# GS2011M.net
KiCad netlist of a schematic drawn in EAGLE
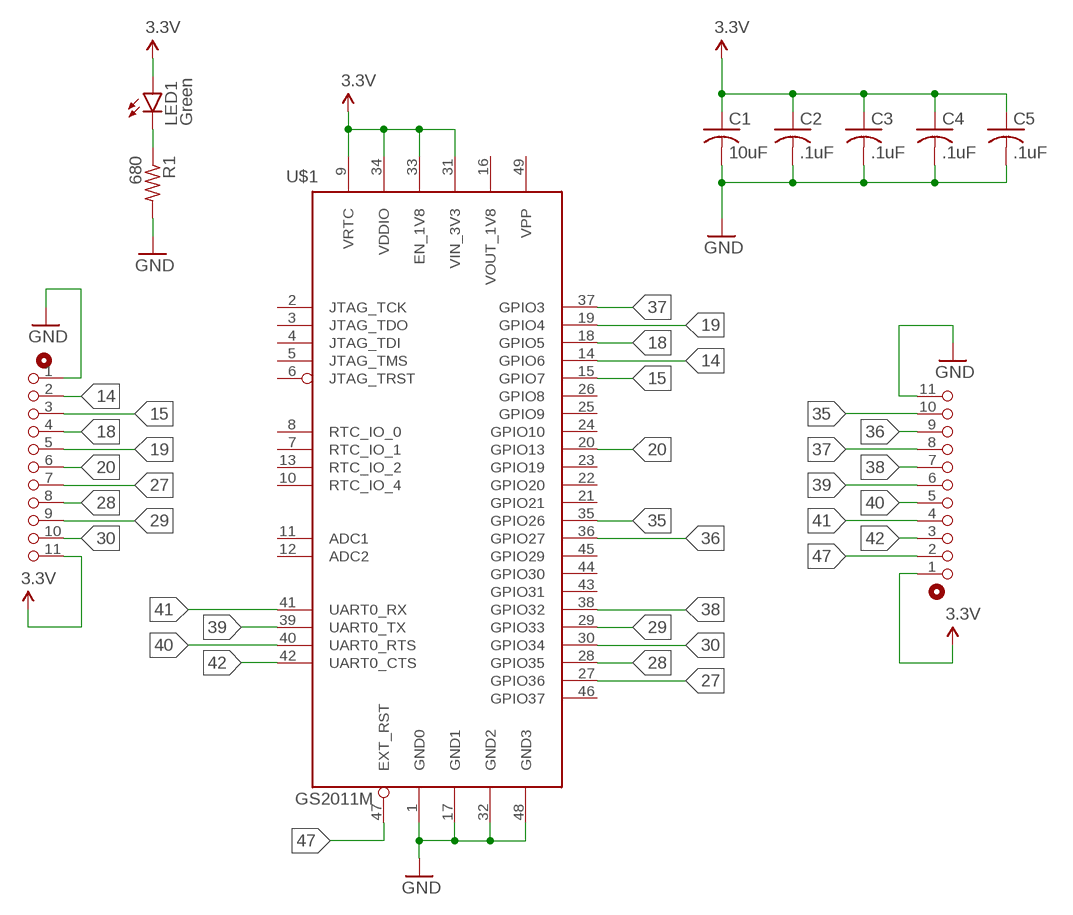
[diagram p0: schematic, sheet 1]

(export (version "E")
  (design (tool "Eeschema 10.0.6"))
  (components
    (comp (ref "C1")
      (value "10uF")
      (footprint "eagle-import:0603_CAP")
      (libsource (lib "eagle-import") (part "CAP0603"))
    )
    (comp (ref "C2")
      (value ".1uF")
      (footprint "eagle-import:0603_CAP")
      (libsource (lib "eagle-import") (part "CAP0603"))
    )
    (comp (ref "C3")
      (value ".1uF")
      (footprint "eagle-import:0603_CAP")
      (libsource (lib "eagle-import") (part "CAP0603"))
    )
    (comp (ref "C4")
      (value ".1uF")
      (footprint "eagle-import:0603_CAP")
      (libsource (lib "eagle-import") (part "CAP0603"))
    )
    (comp (ref "C5")
      (value ".1uF")
      (footprint "eagle-import:0603_CAP")
      (libsource (lib "eagle-import") (part "CAP0603"))
    )
    (comp (ref "LED1")
      (value "Green")
      (footprint "eagle-import:0603_LED")
      (fields (field (name "MANF") "Avago Technologies"))
      (libsource (lib "eagle-import") (part "LED0603"))
    )
    (comp (ref "P1")
      (value "PIN-11X1")
      (footprint "eagle-import:PIN-11X1")
      (libsource (lib "eagle-import") (part "PIN-11X1"))
    )
    (comp (ref "P2")
      (value "PIN-11X1")
      (footprint "eagle-import:PIN-11X1")
      (libsource (lib "eagle-import") (part "PIN-11X1"))
    )
    (comp (ref "R1")
      (value "680")
      (footprint "eagle-import:0603_RESISTOR")
      (libsource (lib "eagle-import") (part "RESISTOR0603"))
    )
    (comp (ref "U$1")
      (value "GS2011M")
      (footprint "eagle-import:GS2011M")
      (libsource (lib "eagle-import") (part "GS2011M"))
    )
  )
  (nets
    (net (code "1") (name "/VOUT_1V8") (class "Default")
      (node (ref "U$1") (pin "16") (pinfunction "VOUT_1V8_16") (pintype "power_in"))
    )
    (net (code "2") (name "3.3V") (class "Default")
      (node (ref "C1") (pin "1") (pinfunction "1_1") (pintype "passive"))
      (node (ref "C2") (pin "1") (pinfunction "1_1") (pintype "passive"))
      (node (ref "C3") (pin "1") (pinfunction "1_1") (pintype "passive"))
      (node (ref "C4") (pin "1") (pinfunction "1_1") (pintype "passive"))
      (node (ref "C5") (pin "1") (pinfunction "1_1") (pintype "passive"))
      (node (ref "LED1") (pin "A") (pinfunction "A_A") (pintype "passive"))
      (node (ref "P1") (pin "11") (pinfunction "11_11") (pintype "passive"))
      (node (ref "P2") (pin "1") (pinfunction "1_1") (pintype "passive"))
      (node (ref "U$1") (pin "31") (pinfunction "VIN_3V3_31") (pintype "power_in"))
      (node (ref "U$1") (pin "33") (pinfunction "EN_1V8_33") (pintype "power_in"))
      (node (ref "U$1") (pin "34") (pinfunction "VDDIO_34") (pintype "power_in"))
      (node (ref "U$1") (pin "9") (pinfunction "VRTC_9") (pintype "power_in"))
    )
    (net (code "3") (name "14") (class "Default")
      (node (ref "P1") (pin "2") (pinfunction "2_2") (pintype "passive"))
      (node (ref "U$1") (pin "14") (pinfunction "GPIO6_14") (pintype "bidirectional"))
    )
    (net (code "4") (name "15") (class "Default")
      (node (ref "P1") (pin "3") (pinfunction "3_3") (pintype "passive"))
      (node (ref "U$1") (pin "15") (pinfunction "GPIO7_15") (pintype "bidirectional"))
    )
    (net (code "5") (name "18") (class "Default")
      (node (ref "P1") (pin "4") (pinfunction "4_4") (pintype "passive"))
      (node (ref "U$1") (pin "18") (pinfunction "GPIO5_18") (pintype "bidirectional"))
    )
    (net (code "6") (name "19") (class "Default")
      (node (ref "P1") (pin "5") (pinfunction "5_5") (pintype "passive"))
      (node (ref "U$1") (pin "19") (pinfunction "GPIO4_19") (pintype "bidirectional"))
    )
    (net (code "7") (name "20") (class "Default")
      (node (ref "P1") (pin "6") (pinfunction "6_6") (pintype "passive"))
      (node (ref "U$1") (pin "20") (pinfunction "GPIO13_20") (pintype "bidirectional"))
    )
    (net (code "8") (name "27") (class "Default")
      (node (ref "P1") (pin "7") (pinfunction "7_7") (pintype "passive"))
      (node (ref "U$1") (pin "27") (pinfunction "GPIO36_27") (pintype "bidirectional"))
    )
    (net (code "9") (name "28") (class "Default")
      (node (ref "P1") (pin "8") (pinfunction "8_8") (pintype "passive"))
      (node (ref "U$1") (pin "28") (pinfunction "GPIO35_28") (pintype "bidirectional"))
    )
    (net (code "10") (name "29") (class "Default")
      (node (ref "P1") (pin "9") (pinfunction "9_9") (pintype "passive"))
      (node (ref "U$1") (pin "29") (pinfunction "GPIO33_29") (pintype "bidirectional"))
    )
    (net (code "11") (name "30") (class "Default")
      (node (ref "P1") (pin "10") (pinfunction "10_10") (pintype "passive"))
      (node (ref "U$1") (pin "30") (pinfunction "GPIO34_30") (pintype "bidirectional"))
    )
    (net (code "12") (name "35") (class "Default")
      (node (ref "P2") (pin "10") (pinfunction "10_10") (pintype "passive"))
      (node (ref "U$1") (pin "35") (pinfunction "GPIO26_35") (pintype "bidirectional"))
    )
    (net (code "13") (name "36") (class "Default")
      (node (ref "P2") (pin "9") (pinfunction "9_9") (pintype "passive"))
      (node (ref "U$1") (pin "36") (pinfunction "GPIO27_36") (pintype "bidirectional"))
    )
    (net (code "14") (name "37") (class "Default")
      (node (ref "P2") (pin "8") (pinfunction "8_8") (pintype "passive"))
      (node (ref "U$1") (pin "37") (pinfunction "GPIO3_37") (pintype "bidirectional"))
    )
    (net (code "15") (name "38") (class "Default")
      (node (ref "P2") (pin "7") (pinfunction "7_7") (pintype "passive"))
      (node (ref "U$1") (pin "38") (pinfunction "GPIO32_38") (pintype "bidirectional"))
    )
    (net (code "16") (name "39") (class "Default")
      (node (ref "P2") (pin "6") (pinfunction "6_6") (pintype "passive"))
      (node (ref "U$1") (pin "39") (pinfunction "UART0_TX_39") (pintype "bidirectional"))
    )
    (net (code "17") (name "40") (class "Default")
      (node (ref "P2") (pin "5") (pinfunction "5_5") (pintype "passive"))
      (node (ref "U$1") (pin "40") (pinfunction "UART0_RTS_40") (pintype "bidirectional"))
    )
    (net (code "18") (name "41") (class "Default")
      (node (ref "P2") (pin "4") (pinfunction "4_4") (pintype "passive"))
      (node (ref "U$1") (pin "41") (pinfunction "UART0_RX_41") (pintype "bidirectional"))
    )
    (net (code "19") (name "42") (class "Default")
      (node (ref "P2") (pin "3") (pinfunction "3_3") (pintype "passive"))
      (node (ref "U$1") (pin "42") (pinfunction "UART0_CTS_42") (pintype "bidirectional"))
    )
    (net (code "20") (name "47") (class "Default")
      (node (ref "P2") (pin "2") (pinfunction "2_2") (pintype "passive"))
      (node (ref "U$1") (pin "47") (pinfunction "EXT_RST_47") (pintype "bidirectional"))
    )
    (net (code "21") (name "GND") (class "Default")
      (node (ref "C1") (pin "2") (pinfunction "2_2") (pintype "passive"))
      (node (ref "C2") (pin "2") (pinfunction "2_2") (pintype "passive"))
      (node (ref "C3") (pin "2") (pinfunction "2_2") (pintype "passive"))
      (node (ref "C4") (pin "2") (pinfunction "2_2") (pintype "passive"))
      (node (ref "C5") (pin "2") (pinfunction "2_2") (pintype "passive"))
      (node (ref "P1") (pin "1") (pinfunction "1_1") (pintype "passive"))
      (node (ref "P2") (pin "11") (pinfunction "11_11") (pintype "passive"))
      (node (ref "R1") (pin "2") (pinfunction "2_2") (pintype "passive"))
      (node (ref "U$1") (pin "1") (pinfunction "GND0_1") (pintype "power_in"))
      (node (ref "U$1") (pin "17") (pinfunction "GND1_17") (pintype "power_in"))
      (node (ref "U$1") (pin "32") (pinfunction "GND2_32") (pintype "power_in"))
      (node (ref "U$1") (pin "48") (pinfunction "GND3_48") (pintype "power_in"))
    )
    (net (code "22") (name "Net-(LED1-PadC)") (class "Default")
      (node (ref "LED1") (pin "C") (pinfunction "C_C") (pintype "passive"))
      (node (ref "R1") (pin "1") (pinfunction "1_1") (pintype "passive"))
    )
    (net (code "23") (name "unconnected-(U$1-ADC1-Pad11)") (class "Default")
      (node (ref "U$1") (pin "11") (pinfunction "ADC1_11") (pintype "passive"))
    )
    (net (code "24") (name "unconnected-(U$1-ADC2-Pad12)") (class "Default")
      (node (ref "U$1") (pin "12") (pinfunction "ADC2_12") (pintype "passive"))
    )
    (net (code "25") (name "unconnected-(U$1-GPIO8-Pad26)") (class "Default")
      (node (ref "U$1") (pin "26") (pinfunction "GPIO8_26") (pintype "bidirectional"))
    )
    (net (code "26") (name "unconnected-(U$1-GPIO9-Pad25)") (class "Default")
      (node (ref "U$1") (pin "25") (pinfunction "GPIO9_25") (pintype "bidirectional"))
    )
    (net (code "27") (name "unconnected-(U$1-GPIO10-Pad24)") (class "Default")
      (node (ref "U$1") (pin "24") (pinfunction "GPIO10_24") (pintype "bidirectional"))
    )
    (net (code "28") (name "unconnected-(U$1-GPIO19-Pad23)") (class "Default")
      (node (ref "U$1") (pin "23") (pinfunction "GPIO19_23") (pintype "bidirectional"))
    )
    (net (code "29") (name "unconnected-(U$1-GPIO20-Pad22)") (class "Default")
      (node (ref "U$1") (pin "22") (pinfunction "GPIO20_22") (pintype "bidirectional"))
    )
    (net (code "30") (name "unconnected-(U$1-GPIO21-Pad21)") (class "Default")
      (node (ref "U$1") (pin "21") (pinfunction "GPIO21_21") (pintype "bidirectional"))
    )
    (net (code "31") (name "unconnected-(U$1-GPIO29-Pad45)") (class "Default")
      (node (ref "U$1") (pin "45") (pinfunction "GPIO29_45") (pintype "bidirectional"))
    )
    (net (code "32") (name "unconnected-(U$1-GPIO30-Pad44)") (class "Default")
      (node (ref "U$1") (pin "44") (pinfunction "GPIO30_44") (pintype "bidirectional"))
    )
    (net (code "33") (name "unconnected-(U$1-GPIO31-Pad43)") (class "Default")
      (node (ref "U$1") (pin "43") (pinfunction "GPIO31_43") (pintype "bidirectional"))
    )
    (net (code "34") (name "unconnected-(U$1-GPIO37-Pad46)") (class "Default")
      (node (ref "U$1") (pin "46") (pinfunction "GPIO37_46") (pintype "bidirectional"))
    )
    (net (code "35") (name "unconnected-(U$1-JTAG_TCK-Pad2)") (class "Default")
      (node (ref "U$1") (pin "2") (pinfunction "JTAG_TCK_2") (pintype "input"))
    )
    (net (code "36") (name "unconnected-(U$1-JTAG_TDI-Pad4)") (class "Default")
      (node (ref "U$1") (pin "4") (pinfunction "JTAG_TDI_4") (pintype "input"))
    )
    (net (code "37") (name "unconnected-(U$1-JTAG_TDO-Pad3)") (class "Default")
      (node (ref "U$1") (pin "3") (pinfunction "JTAG_TDO_3") (pintype "output"))
    )
    (net (code "38") (name "unconnected-(U$1-JTAG_TMS-Pad5)") (class "Default")
      (node (ref "U$1") (pin "5") (pinfunction "JTAG_TMS_5") (pintype "input"))
    )
    (net (code "39") (name "unconnected-(U$1-JTAG_TRST-Pad6)") (class "Default")
      (node (ref "U$1") (pin "6") (pinfunction "JTAG_TRST_6") (pintype "input"))
    )
    (net (code "40") (name "unconnected-(U$1-RTC_IO_0-Pad8)") (class "Default")
      (node (ref "U$1") (pin "8") (pinfunction "RTC_IO_0_8") (pintype "bidirectional"))
    )
    (net (code "41") (name "unconnected-(U$1-RTC_IO_1-Pad7)") (class "Default")
      (node (ref "U$1") (pin "7") (pinfunction "RTC_IO_1_7") (pintype "bidirectional"))
    )
    (net (code "42") (name "unconnected-(U$1-RTC_IO_2-Pad13)") (class "Default")
      (node (ref "U$1") (pin "13") (pinfunction "RTC_IO_2_13") (pintype "bidirectional"))
    )
    (net (code "43") (name "unconnected-(U$1-RTC_IO_4-Pad10)") (class "Default")
      (node (ref "U$1") (pin "10") (pinfunction "RTC_IO_4_10") (pintype "bidirectional"))
    )
    (net (code "44") (name "unconnected-(U$1-VPP-Pad49)") (class "Default")
      (node (ref "U$1") (pin "49") (pinfunction "VPP_49") (pintype "passive"))
    )
  )
)
